# USBserial.net
KiCad netlist of a schematic drawn in Altium Designer
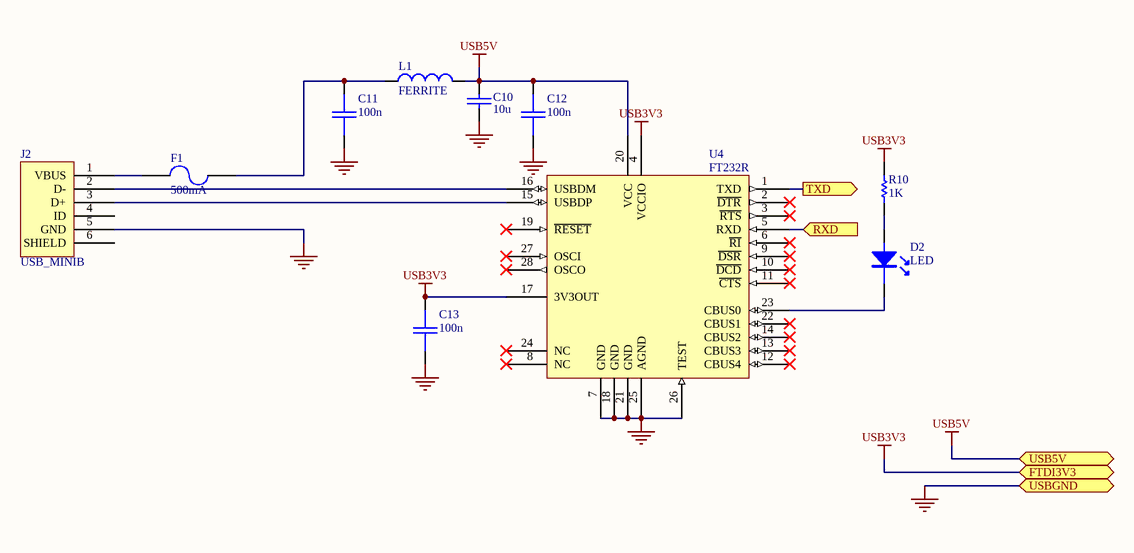
[diagram p0: USBserial.SchDoc]

(export (version "E")
  (design (tool "Eeschema 10.0.6"))
  (components
    (comp (ref "C10")
      (value "10u")
      (footprint "0805")
      (description "Capacitor")
      (libsource (lib "*") (part "CAP"))
    )
    (comp (ref "C11")
      (value "100n")
      (footprint "0603")
      (description "Capacitor")
      (libsource (lib "RCLDQ") (part "CAP"))
    )
    (comp (ref "C12")
      (value "100n")
      (footprint "0603")
      (description "Capacitor")
      (libsource (lib "RCLDQ") (part "CAP"))
    )
    (comp (ref "C13")
      (value "100n")
      (footprint "0603")
      (description "Capacitor")
      (libsource (lib "RCLDQ") (part "CAP"))
    )
    (comp (ref "D2") (value "LED") (footprint "0805LED") (libsource (lib "RCLDQ") (part "LED")))
    (comp (ref "F1")
      (value "500mA")
      (footprint "LITTELFUSE-154")
      (description "Fuse")
      (libsource (lib "*") (part "FUSE2"))
    )
    (comp (ref "J2")
      (value "USB_MINIB")
      (footprint "Con USB:USB/SM0.8-6H5")
      (description "USB Mini B Connector")
      (libsource (lib "sion") (part "USB_miniB_SMT"))
    )
    (comp (ref "L1")
      (value "FERRITE")
      (footprint "0603")
      (description "Inductor")
      (fields (field (name "MANUFACTURER") "Generic Components"))
      (libsource (lib "RCLDQ") (part "INDUCTOR"))
    )
    (comp (ref "R10")
      (value "1K")
      (footprint "0603")
      (description "Semiconductor Resistor")
      (libsource (lib "Miscellaneous Devices") (part "Res Semi"))
    )
    (comp (ref "U4")
      (value "FT232R")
      (footprint "SSOP28w")
      (description "USB UART IC")
      (libsource (lib "MiscellaneousIC") (part "FT232R"))
    )
  )
  (nets
    (net (code "1") (name "/RXD") (class "Default")
      (node (ref "U4") (pin "5") (pinfunction "RXD_5") (pintype "input"))
    )
    (net (code "2") (name "/TXD") (class "Default")
      (node (ref "U4") (pin "1") (pinfunction "TXD_1") (pintype "output"))
    )
    (net (code "3") (name "Net-(C11-Pad1)") (class "Default")
      (node (ref "C11") (pin "1") (pinfunction "1_1") (pintype "passive"))
      (node (ref "F1") (pin "2") (pinfunction "2_2") (pintype "passive"))
      (node (ref "L1") (pin "1") (pinfunction "1_1") (pintype "passive"))
    )
    (net (code "4") (name "Net-(D2-PadA)") (class "Default")
      (node (ref "D2") (pin "A") (pinfunction "A_A") (pintype "passive"))
      (node (ref "R10") (pin "1") (pinfunction "1_1") (pintype "passive"))
    )
    (net (code "5") (name "Net-(J2-D+)") (class "Default")
      (node (ref "J2") (pin "3") (pinfunction "D+_3") (pintype "passive"))
      (node (ref "U4") (pin "15") (pinfunction "USBDP_15") (pintype "bidirectional"))
    )
    (net (code "6") (name "Net-(J2-D-)") (class "Default")
      (node (ref "J2") (pin "2") (pinfunction "D-_2") (pintype "passive"))
      (node (ref "U4") (pin "16") (pinfunction "USBDM_16") (pintype "bidirectional"))
    )
    (net (code "7") (name "Net-(J2-VBUS)") (class "Default")
      (node (ref "F1") (pin "1") (pinfunction "1_1") (pintype "passive"))
      (node (ref "J2") (pin "1") (pinfunction "VBUS_1") (pintype "passive"))
    )
    (net (code "8") (name "Net-(U4-CBUS0)") (class "Default")
      (node (ref "D2") (pin "K") (pinfunction "K_K") (pintype "passive"))
      (node (ref "U4") (pin "23") (pinfunction "CBUS0_23") (pintype "bidirectional"))
    )
    (net (code "9") (name "USB3V3") (class "Default")
      (node (ref "C13") (pin "1") (pinfunction "1_1") (pintype "passive"))
      (node (ref "R10") (pin "2") (pinfunction "2_2") (pintype "passive"))
      (node (ref "U4") (pin "17") (pinfunction "3V3OUT_17") (pintype "power_in"))
      (node (ref "U4") (pin "4") (pinfunction "VCCIO_4") (pintype "power_in"))
    )
    (net (code "10") (name "USB5V") (class "Default")
      (node (ref "C10") (pin "2") (pinfunction "2_2") (pintype "passive"))
      (node (ref "C12") (pin "1") (pinfunction "1_1") (pintype "passive"))
      (node (ref "L1") (pin "2") (pinfunction "2_2") (pintype "passive"))
      (node (ref "U4") (pin "20") (pinfunction "VCC_20") (pintype "power_in"))
    )
    (net (code "11") (name "USBGND") (class "Default")
      (node (ref "C10") (pin "1") (pinfunction "1_1") (pintype "passive"))
      (node (ref "C11") (pin "2") (pinfunction "2_2") (pintype "passive"))
      (node (ref "C12") (pin "2") (pinfunction "2_2") (pintype "passive"))
      (node (ref "C13") (pin "2") (pinfunction "2_2") (pintype "passive"))
      (node (ref "J2") (pin "5") (pinfunction "GND_5") (pintype "passive"))
      (node (ref "U4") (pin "18") (pinfunction "GND_18") (pintype "power_in"))
      (node (ref "U4") (pin "21") (pinfunction "GND_21") (pintype "power_in"))
      (node (ref "U4") (pin "25") (pinfunction "AGND_25") (pintype "power_in"))
      (node (ref "U4") (pin "26") (pinfunction "TEST_26") (pintype "input"))
      (node (ref "U4") (pin "7") (pinfunction "GND_7") (pintype "power_in"))
    )
    (net (code "12") (name "unconnected-(J2-ID-Pad4)") (class "Default")
      (node (ref "J2") (pin "4") (pinfunction "ID_4") (pintype "passive"))
    )
    (net (code "13") (name "unconnected-(J2-SHIELD-Pad6)") (class "Default")
      (node (ref "J2") (pin "6") (pinfunction "SHIELD_6") (pintype "passive"))
    )
    (net (code "14") (name "unconnected-(U4-CBUS1-Pad22)") (class "Default")
      (node (ref "U4") (pin "22") (pinfunction "CBUS1_22") (pintype "bidirectional+no_connect"))
    )
    (net (code "15") (name "unconnected-(U4-CBUS2-Pad14)") (class "Default")
      (node (ref "U4") (pin "14") (pinfunction "CBUS2_14") (pintype "bidirectional+no_connect"))
    )
    (net (code "16") (name "unconnected-(U4-CBUS3-Pad13)") (class "Default")
      (node (ref "U4") (pin "13") (pinfunction "CBUS3_13") (pintype "bidirectional+no_connect"))
    )
    (net (code "17") (name "unconnected-(U4-CBUS4-Pad12)") (class "Default")
      (node (ref "U4") (pin "12") (pinfunction "CBUS4_12") (pintype "bidirectional+no_connect"))
    )
    (net (code "18") (name "unconnected-(U4-NC-Pad8)") (class "Default")
      (node (ref "U4") (pin "8") (pinfunction "NC_8") (pintype "passive+no_connect"))
    )
    (net (code "19") (name "unconnected-(U4-NC-Pad24)") (class "Default")
      (node (ref "U4") (pin "24") (pinfunction "NC_24") (pintype "passive+no_connect"))
    )
    (net (code "20") (name "unconnected-(U4-OSCI-Pad27)") (class "Default")
      (node (ref "U4") (pin "27") (pinfunction "OSCI_27") (pintype "input+no_connect"))
    )
    (net (code "21") (name "unconnected-(U4-OSCO-Pad28)") (class "Default")
      (node (ref "U4") (pin "28") (pinfunction "OSCO_28") (pintype "output+no_connect"))
    )
    (net (code "22") (name "unconnected-(U4-~{CTS}-Pad11)") (class "Default")
      (node (ref "U4") (pin "11") (pinfunction "~{CTS}_11") (pintype "input+no_connect"))
    )
    (net (code "23") (name "unconnected-(U4-~{DCD}-Pad10)") (class "Default")
      (node (ref "U4") (pin "10") (pinfunction "~{DCD}_10") (pintype "input+no_connect"))
    )
    (net (code "24") (name "unconnected-(U4-~{DSR}-Pad9)") (class "Default")
      (node (ref "U4") (pin "9") (pinfunction "~{DSR}_9") (pintype "input+no_connect"))
    )
    (net (code "25") (name "unconnected-(U4-~{DTR}-Pad2)") (class "Default")
      (node (ref "U4") (pin "2") (pinfunction "~{DTR}_2") (pintype "output+no_connect"))
    )
    (net (code "26") (name "unconnected-(U4-~{RESET}-Pad19)") (class "Default")
      (node (ref "U4") (pin "19") (pinfunction "~{RESET}_19") (pintype "input+no_connect"))
    )
    (net (code "27") (name "unconnected-(U4-~{RI}-Pad6)") (class "Default")
      (node (ref "U4") (pin "6") (pinfunction "~{RI}_6") (pintype "input+no_connect"))
    )
    (net (code "28") (name "unconnected-(U4-~{RTS}-Pad3)") (class "Default")
      (node (ref "U4") (pin "3") (pinfunction "~{RTS}_3") (pintype "output+no_connect"))
    )
  )
)
